# Noise_Sheet1.net
KiCad netlist of a schematic drawn in Altium Designer
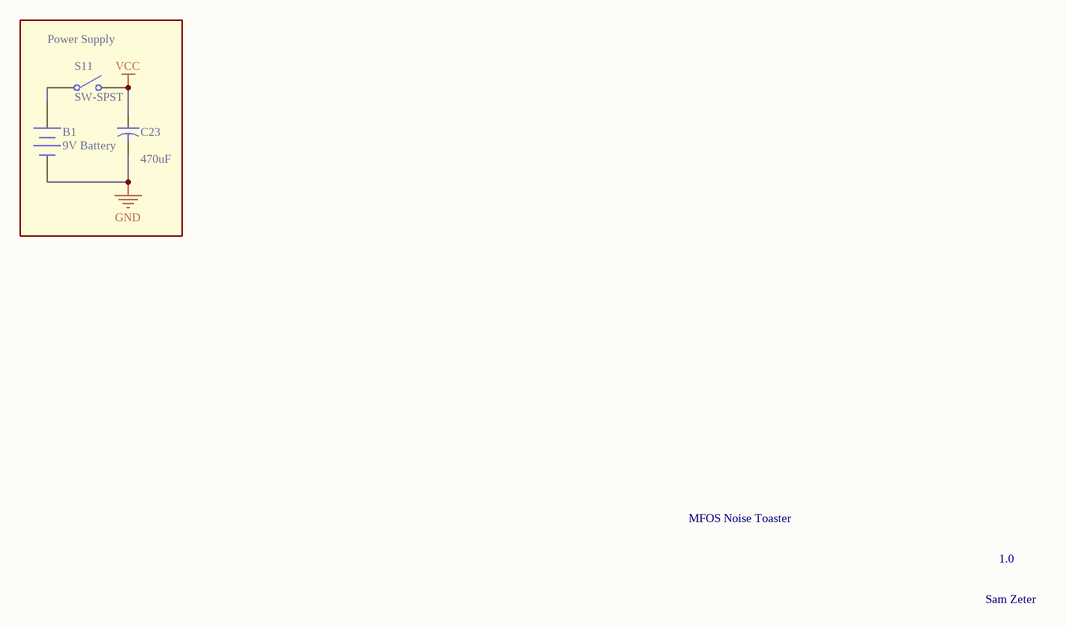
[diagram p0: Noise_Sheet1.SchDoc]

(export (version "E")
  (design (tool "Eeschema 10.0.6"))
  (components
    (comp (ref "B1")
      (value "9V Battery")
      (footprint "BAT-2")
      (description "Multicell Battery")
      (fields (field (name "PUBLISHER") "Altium Limited"))
      (libsource (lib "Miscellaneous Devices") (part "Battery"))
    )
    (comp (ref "C23")
      (value "470uF")
      (footprint "CAPR5-4X5")
      (description "Capacitor")
      (fields (field (name "Comment") "Cap2") (field (name "PUBLISHER") "Altium Limited"))
      (libsource (lib "Miscellaneous Devices") (part "Cap2"))
    )
    (comp (ref "S11")
      (value "SW-SPST")
      (footprint "SPST-2")
      (description "Single-Pole, Single-Throw Switch")
      (fields (field (name "PUBLISHER") "Altium Limited"))
      (libsource (lib "Miscellaneous Devices") (part "SW-SPST"))
    )
  )
  (nets
    (net (code "1") (name "GND") (class "Default")
      (node (ref "B1") (pin "2") (pinfunction "-_2") (pintype "passive"))
      (node (ref "C23") (pin "2") (pinfunction "2_2") (pintype "passive"))
    )
    (net (code "2") (name "Net-(B1-+)") (class "Default")
      (node (ref "B1") (pin "1") (pinfunction "+_1") (pintype "passive"))
      (node (ref "S11") (pin "1") (pinfunction "COMMON_1") (pintype "passive"))
    )
    (net (code "3") (name "VCC") (class "Default")
      (node (ref "C23") (pin "1") (pinfunction "1_1") (pintype "passive"))
      (node (ref "S11") (pin "2") (pinfunction "NO_2") (pintype "passive"))
    )
  )
)
